# M_D_ext_power_1A.net
KiCad netlist of a schematic drawn in EAGLE
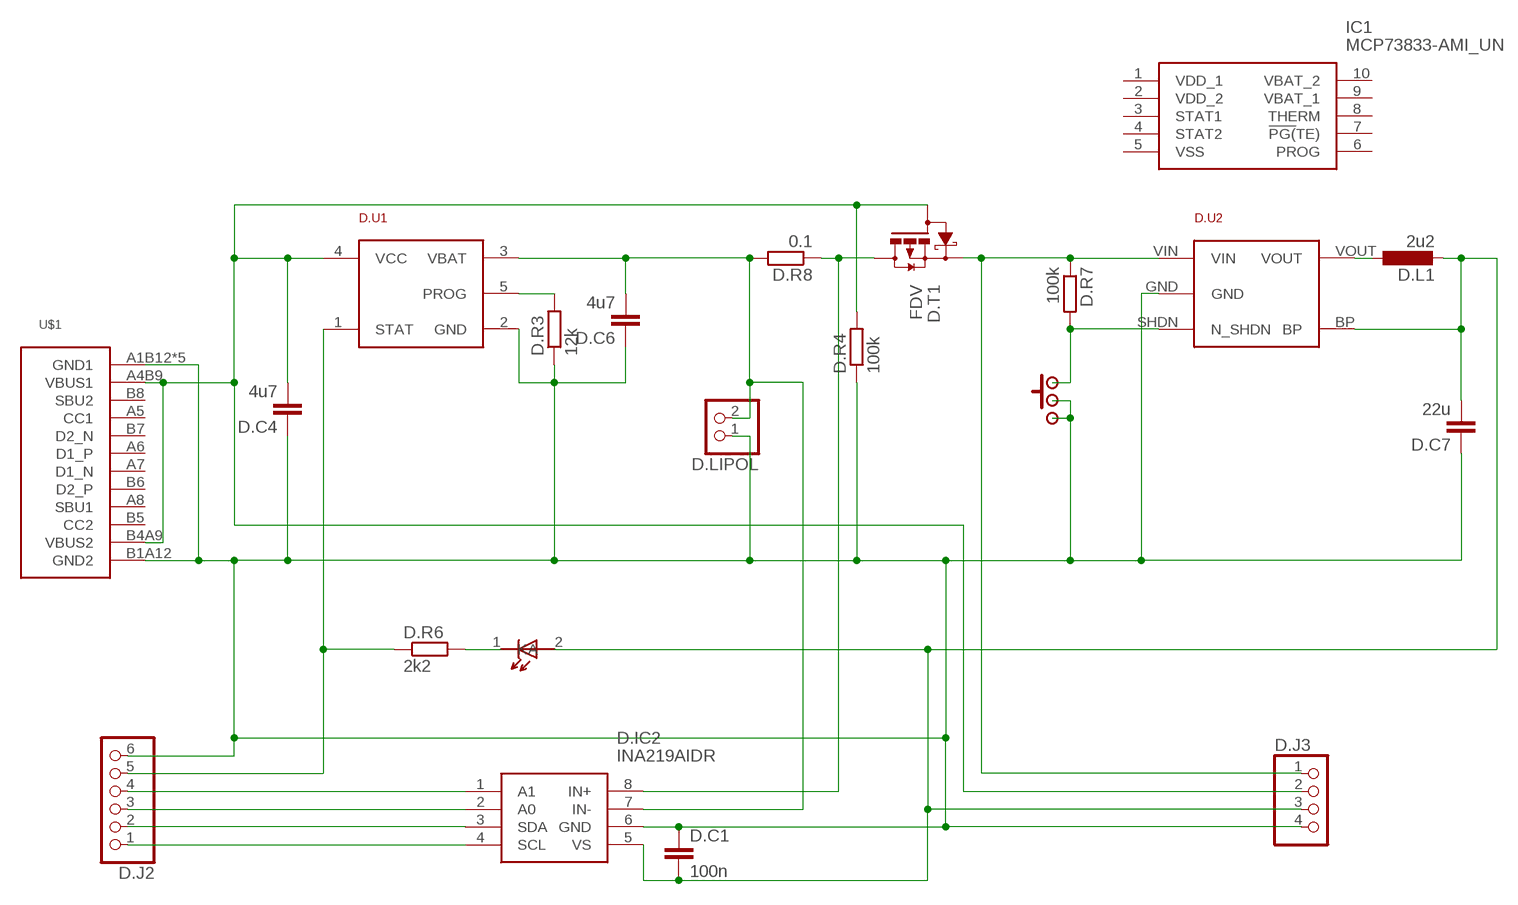
[diagram p0: schematic, sheet 1]

(export (version "E")
  (design (tool "Eeschema 10.0.6"))
  (components
    (comp (ref "D.C1")
      (value "100n")
      (footprint "eagle-import:C0603")
      (libsource (lib "eagle-import") (part "C-EUC0603"))
    )
    (comp (ref "D.C4")
      (value "4u7")
      (footprint "eagle-import:C0603")
      (libsource (lib "eagle-import") (part "C-EUC0603"))
    )
    (comp (ref "D.C6")
      (value "4u7")
      (footprint "eagle-import:C0603")
      (libsource (lib "eagle-import") (part "C-EUC0603"))
    )
    (comp (ref "D.C7")
      (value "22u")
      (footprint "eagle-import:C0805")
      (libsource (lib "eagle-import") (part "C-EUC0805"))
    )
    (comp (ref "D.D1")
      (value "LED_1.8")
      (footprint "eagle-import:LED_1.8")
      (libsource (lib "eagle-import") (part "LED_1.8"))
    )
    (comp (ref "D.IC2")
      (value "INA219AIDR")
      (footprint "eagle-import:SOIC127P600X175-8N")
      (fields (field (name "MOUSER_PART_NUMBER") "595-INA219AIDR"))
      (libsource (lib "eagle-import") (part "INA219AIDR"))
    )
    (comp (ref "D.J2")
      (value "PINHD-1X6")
      (footprint "eagle-import:1X06")
      (libsource (lib "eagle-import") (part "PINHD-1X6"))
    )
    (comp (ref "D.J3")
      (value "PINHD-1X4")
      (footprint "eagle-import:1X04")
      (libsource (lib "eagle-import") (part "PINHD-1X4"))
    )
    (comp (ref "D.L1")
      (value "2u2")
      (footprint "eagle-import:L3230M")
      (libsource (lib "eagle-import") (part "L-EUL3230M"))
    )
    (comp (ref "D.LIPOL")
      (value "PINHD-1X2")
      (footprint "eagle-import:1X02")
      (libsource (lib "eagle-import") (part "PINHD-1X2"))
    )
    (comp (ref "D.ON/OFF/RESET")
      (value "SWITCH")
      (footprint "eagle-import:SWITCH")
      (libsource (lib "eagle-import") (part "SWITCH"))
    )
    (comp (ref "D.R3")
      (value "12k")
      (footprint "eagle-import:R0603")
      (libsource (lib "eagle-import") (part "R-EU_R0603"))
    )
    (comp (ref "D.R4")
      (value "100k")
      (footprint "eagle-import:R0603")
      (libsource (lib "eagle-import") (part "R-EU_R0603"))
    )
    (comp (ref "D.R6")
      (value "2k2")
      (footprint "eagle-import:R0603")
      (libsource (lib "eagle-import") (part "R-EU_R0603"))
    )
    (comp (ref "D.R7")
      (value "100k")
      (footprint "eagle-import:R0603")
      (libsource (lib "eagle-import") (part "R-EU_R0603"))
    )
    (comp (ref "D.R8")
      (value "0.1")
      (footprint "eagle-import:R0805")
      (libsource (lib "eagle-import") (part "R-EU_R0805"))
    )
    (comp (ref "D.T1")
      (value "FDV")
      (footprint "eagle-import:SOT23")
      (libsource (lib "eagle-import") (part "P-MOSFET-FDV304P"))
    )
    (comp (ref "D.U1")
      (value "MCP")
      (footprint "eagle-import:SOT23-5")
      (libsource (lib "eagle-import") (part "MCP73831"))
    )
    (comp (ref "D.U2")
      (value "TC")
      (footprint "eagle-import:SOT32-5")
      (libsource (lib "eagle-import") (part "STABILISER_APE8865"))
    )
    (comp (ref "IC1")
      (value "MCP73833-AMI_UN")
      (footprint "eagle-import:SOP50P490X110-10N")
      (fields
        (field (name "MANUFACTURER_PART_NUMBER") "MCP73833-AMI/UN")
        (field (name "MOUSER_PART_NUMBER") "579-MCP73833-AMI/UN")
      )
      (libsource (lib "eagle-import") (part "MCP73833-AMI_UN"))
    )
    (comp (ref "U$1")
      (value "USB-C")
      (footprint "eagle-import:USB-C")
      (libsource (lib "eagle-import") (part "USB-C"))
    )
  )
  (nets
    (net (code "1") (name "Net-(D.D1-A)") (class "Default")
      (node (ref "D.C1") (pin "2") (pinfunction "2_2") (pintype "passive"))
      (node (ref "D.C7") (pin "2") (pinfunction "2_2") (pintype "passive"))
      (node (ref "D.D1") (pin "2") (pinfunction "A_2") (pintype "bidirectional"))
      (node (ref "D.IC2") (pin "5") (pinfunction "VS_5") (pintype "bidirectional"))
      (node (ref "D.J3") (pin "3") (pinfunction "3_3") (pintype "passive"))
      (node (ref "D.L1") (pin "2") (pinfunction "2_2") (pintype "passive"))
      (node (ref "D.U2") (pin "BP") (pinfunction "BP_BP") (pintype "bidirectional"))
    )
    (net (code "2") (name "Net-(D.D1-K)") (class "Default")
      (node (ref "D.D1") (pin "1") (pinfunction "K_1") (pintype "bidirectional"))
      (node (ref "D.R6") (pin "2") (pinfunction "2_2") (pintype "passive"))
    )
    (net (code "3") (name "Net-(D.IC2-A0)") (class "Default")
      (node (ref "D.IC2") (pin "2") (pinfunction "A0_2") (pintype "bidirectional"))
      (node (ref "D.J2") (pin "3") (pinfunction "3_3") (pintype "passive"))
    )
    (net (code "4") (name "Net-(D.IC2-A1)") (class "Default")
      (node (ref "D.IC2") (pin "1") (pinfunction "A1_1") (pintype "bidirectional"))
      (node (ref "D.J2") (pin "4") (pinfunction "4_4") (pintype "passive"))
    )
    (net (code "5") (name "Net-(D.IC2-GND)") (class "Default")
      (node (ref "D.C1") (pin "1") (pinfunction "1_1") (pintype "passive"))
      (node (ref "D.C4") (pin "1") (pinfunction "1_1") (pintype "passive"))
      (node (ref "D.C6") (pin "1") (pinfunction "1_1") (pintype "passive"))
      (node (ref "D.C7") (pin "1") (pinfunction "1_1") (pintype "passive"))
      (node (ref "D.IC2") (pin "6") (pinfunction "GND_6") (pintype "bidirectional"))
      (node (ref "D.J2") (pin "6") (pinfunction "6_6") (pintype "passive"))
      (node (ref "D.J3") (pin "4") (pinfunction "4_4") (pintype "passive"))
      (node (ref "D.LIPOL") (pin "1") (pinfunction "1_1") (pintype "passive"))
      (node (ref "D.ON/OFF/RESET") (pin "P$2") (pinfunction "P$2_P$2") (pintype "bidirectional"))
      (node (ref "D.ON/OFF/RESET") (pin "P$3") (pinfunction "P$3_P$3") (pintype "bidirectional"))
      (node (ref "D.ON/OFF/RESET") (pin "P$5") (pinfunction "P$3_P$5") (pintype "bidirectional"))
      (node (ref "D.R3") (pin "1") (pinfunction "1_1") (pintype "passive"))
      (node (ref "D.R4") (pin "1") (pinfunction "1_1") (pintype "passive"))
      (node (ref "D.U1") (pin "2") (pinfunction "GND_2") (pintype "bidirectional"))
      (node (ref "D.U2") (pin "GND") (pinfunction "GND_GND") (pintype "bidirectional"))
      (node (ref "U$1") (pin "A1B12") (pinfunction "GND1_A1B12") (pintype "bidirectional"))
      (node (ref "U$1") (pin "B1A12") (pinfunction "GND2_B1A12") (pintype "bidirectional"))
      (node (ref "U$1") (pin "SH1") (pinfunction "GND1_SH1") (pintype "bidirectional"))
      (node (ref "U$1") (pin "SH2") (pinfunction "GND1_SH2") (pintype "bidirectional"))
      (node (ref "U$1") (pin "SH3") (pinfunction "GND1_SH3") (pintype "bidirectional"))
      (node (ref "U$1") (pin "SH4") (pinfunction "GND1_SH4") (pintype "bidirectional"))
    )
    (net (code "6") (name "Net-(D.IC2-IN+)") (class "Default")
      (node (ref "D.IC2") (pin "8") (pinfunction "IN+_8") (pintype "bidirectional"))
      (node (ref "D.R8") (pin "1") (pinfunction "1_1") (pintype "passive"))
      (node (ref "D.T1") (pin "D") (pinfunction "D_D") (pintype "passive"))
    )
    (net (code "7") (name "Net-(D.IC2-IN-)") (class "Default")
      (node (ref "D.C6") (pin "2") (pinfunction "2_2") (pintype "passive"))
      (node (ref "D.IC2") (pin "7") (pinfunction "IN-_7") (pintype "bidirectional"))
      (node (ref "D.LIPOL") (pin "2") (pinfunction "2_2") (pintype "passive"))
      (node (ref "D.R8") (pin "2") (pinfunction "2_2") (pintype "passive"))
      (node (ref "D.U1") (pin "3") (pinfunction "VBAT_3") (pintype "bidirectional"))
    )
    (net (code "8") (name "Net-(D.IC2-SCL)") (class "Default")
      (node (ref "D.IC2") (pin "4") (pinfunction "SCL_4") (pintype "bidirectional"))
      (node (ref "D.J2") (pin "1") (pinfunction "1_1") (pintype "passive"))
    )
    (net (code "9") (name "Net-(D.IC2-SDA)") (class "Default")
      (node (ref "D.IC2") (pin "3") (pinfunction "SDA_3") (pintype "bidirectional"))
      (node (ref "D.J2") (pin "2") (pinfunction "2_2") (pintype "passive"))
    )
    (net (code "10") (name "Net-(D.J3-Pad1)") (class "Default")
      (node (ref "D.J3") (pin "1") (pinfunction "1_1") (pintype "passive"))
      (node (ref "D.R7") (pin "1") (pinfunction "1_1") (pintype "passive"))
      (node (ref "D.T1") (pin "S") (pinfunction "S_S") (pintype "passive"))
      (node (ref "D.U2") (pin "VIN") (pinfunction "VIN_VIN") (pintype "bidirectional"))
    )
    (net (code "11") (name "Net-(D.L1-Pad1)") (class "Default")
      (node (ref "D.L1") (pin "1") (pinfunction "1_1") (pintype "passive"))
      (node (ref "D.U2") (pin "VOUT") (pinfunction "VOUT_VOUT") (pintype "bidirectional"))
    )
    (net (code "12") (name "Net-(D.U1-PROG)") (class "Default")
      (node (ref "D.R3") (pin "2") (pinfunction "2_2") (pintype "passive"))
      (node (ref "D.U1") (pin "5") (pinfunction "PROG_5") (pintype "bidirectional"))
    )
    (net (code "13") (name "Net-(D.U1-STAT)") (class "Default")
      (node (ref "D.J2") (pin "5") (pinfunction "5_5") (pintype "passive"))
      (node (ref "D.R6") (pin "1") (pinfunction "1_1") (pintype "passive"))
      (node (ref "D.U1") (pin "1") (pinfunction "STAT_1") (pintype "bidirectional"))
    )
    (net (code "14") (name "Net-(D.U1-VCC)") (class "Default")
      (node (ref "D.C4") (pin "2") (pinfunction "2_2") (pintype "passive"))
      (node (ref "D.J3") (pin "2") (pinfunction "2_2") (pintype "passive"))
      (node (ref "D.R4") (pin "2") (pinfunction "2_2") (pintype "passive"))
      (node (ref "D.T1") (pin "G") (pinfunction "G_G") (pintype "passive"))
      (node (ref "D.U1") (pin "4") (pinfunction "VCC_4") (pintype "bidirectional"))
      (node (ref "U$1") (pin "A4B9") (pinfunction "VBUS1_A4B9") (pintype "bidirectional"))
      (node (ref "U$1") (pin "B4A9") (pinfunction "VBUS2_B4A9") (pintype "bidirectional"))
    )
    (net (code "15") (name "Net-(D.U2-N_SHDN)") (class "Default")
      (node (ref "D.ON/OFF/RESET") (pin "P$1") (pinfunction "P$1_P$1") (pintype "bidirectional"))
      (node (ref "D.ON/OFF/RESET") (pin "P$4") (pinfunction "P$1_P$4") (pintype "bidirectional"))
      (node (ref "D.R7") (pin "2") (pinfunction "2_2") (pintype "passive"))
      (node (ref "D.U2") (pin "SHDN") (pinfunction "N_SHDN_SHDN") (pintype "bidirectional"))
    )
    (net (code "16") (name "unconnected-(IC1-PROG-Pad6)") (class "Default")
      (node (ref "IC1") (pin "6") (pinfunction "PROG_6") (pintype "bidirectional"))
    )
    (net (code "17") (name "unconnected-(IC1-STAT1-Pad3)") (class "Default")
      (node (ref "IC1") (pin "3") (pinfunction "STAT1_3") (pintype "bidirectional"))
    )
    (net (code "18") (name "unconnected-(IC1-STAT2-Pad4)") (class "Default")
      (node (ref "IC1") (pin "4") (pinfunction "STAT2_4") (pintype "bidirectional"))
    )
    (net (code "19") (name "unconnected-(IC1-THERM-Pad8)") (class "Default")
      (node (ref "IC1") (pin "8") (pinfunction "THERM_8") (pintype "bidirectional"))
    )
    (net (code "20") (name "unconnected-(IC1-VBAT_1-Pad9)") (class "Default")
      (node (ref "IC1") (pin "9") (pinfunction "VBAT_1_9") (pintype "bidirectional"))
    )
    (net (code "21") (name "unconnected-(IC1-VBAT_2-Pad10)") (class "Default")
      (node (ref "IC1") (pin "10") (pinfunction "VBAT_2_10") (pintype "bidirectional"))
    )
    (net (code "22") (name "unconnected-(IC1-VDD_1-Pad1)") (class "Default")
      (node (ref "IC1") (pin "1") (pinfunction "VDD_1_1") (pintype "bidirectional"))
    )
    (net (code "23") (name "unconnected-(IC1-VDD_2-Pad2)") (class "Default")
      (node (ref "IC1") (pin "2") (pinfunction "VDD_2_2") (pintype "bidirectional"))
    )
    (net (code "24") (name "unconnected-(IC1-VSS-Pad5)") (class "Default")
      (node (ref "IC1") (pin "5") (pinfunction "VSS_5") (pintype "bidirectional"))
    )
    (net (code "25") (name "unconnected-(IC1-~{PG(}TE)-Pad7)") (class "Default")
      (node (ref "IC1") (pin "7") (pinfunction "~{PG(}TE)_7") (pintype "bidirectional"))
    )
    (net (code "26") (name "unconnected-(U$1-CC1-PadA5)") (class "Default")
      (node (ref "U$1") (pin "A5") (pinfunction "CC1_A5") (pintype "bidirectional"))
    )
    (net (code "27") (name "unconnected-(U$1-CC2-PadB5)") (class "Default")
      (node (ref "U$1") (pin "B5") (pinfunction "CC2_B5") (pintype "bidirectional"))
    )
    (net (code "28") (name "unconnected-(U$1-D1_N-PadA7)") (class "Default")
      (node (ref "U$1") (pin "A7") (pinfunction "D1_N_A7") (pintype "bidirectional"))
    )
    (net (code "29") (name "unconnected-(U$1-D1_P-PadA6)") (class "Default")
      (node (ref "U$1") (pin "A6") (pinfunction "D1_P_A6") (pintype "bidirectional"))
    )
    (net (code "30") (name "unconnected-(U$1-D2_N-PadB7)") (class "Default")
      (node (ref "U$1") (pin "B7") (pinfunction "D2_N_B7") (pintype "bidirectional"))
    )
    (net (code "31") (name "unconnected-(U$1-D2_P-PadB6)") (class "Default")
      (node (ref "U$1") (pin "B6") (pinfunction "D2_P_B6") (pintype "bidirectional"))
    )
    (net (code "32") (name "unconnected-(U$1-SBU1-PadA8)") (class "Default")
      (node (ref "U$1") (pin "A8") (pinfunction "SBU1_A8") (pintype "bidirectional"))
    )
    (net (code "33") (name "unconnected-(U$1-SBU2-PadB8)") (class "Default")
      (node (ref "U$1") (pin "B8") (pinfunction "SBU2_B8") (pintype "bidirectional"))
    )
  )
)
